# CONN.net
KiCad netlist of a schematic drawn in Altium Designer
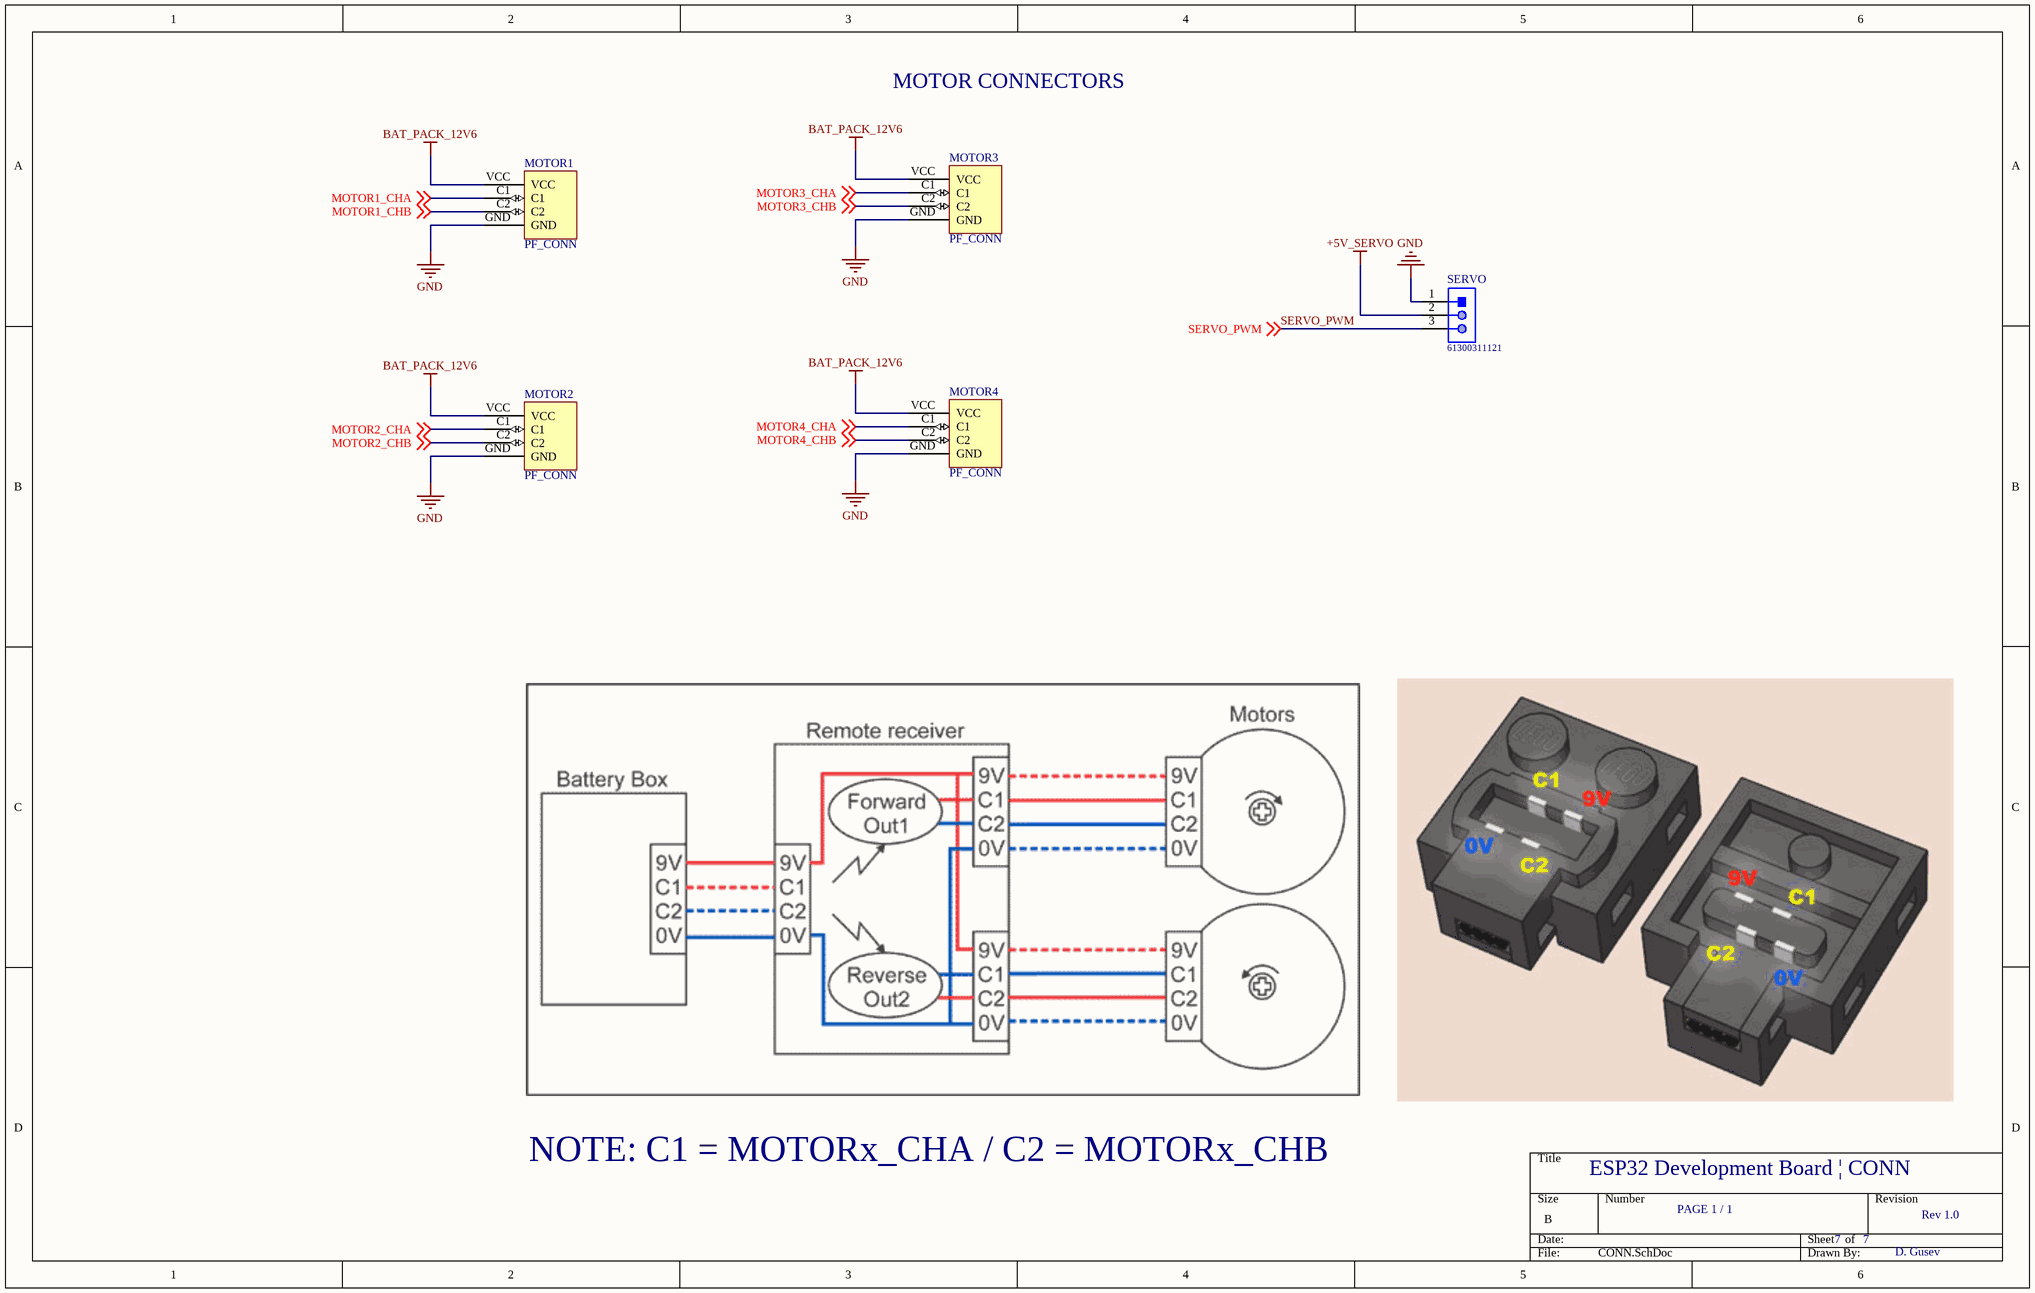
[diagram p0: CONN.SchDoc]

(export (version "E")
  (design (tool "Eeschema 10.0.6"))
  (components
    (comp (ref "MOTOR1")
      (value "PF_CONN")
      (footprint "PF_CONN")
      (libsource (lib "ddrlegobrick") (part "PF_CONN"))
    )
    (comp (ref "MOTOR2")
      (value "PF_CONN")
      (footprint "PF_CONN")
      (libsource (lib "ddrlegobrick") (part "PF_CONN"))
    )
    (comp (ref "MOTOR3")
      (value "PF_CONN")
      (footprint "PF_CONN")
      (libsource (lib "ddrlegobrick") (part "PF_CONN"))
    )
    (comp (ref "MOTOR4")
      (value "PF_CONN")
      (footprint "PF_CONN")
      (libsource (lib "ddrlegobrick") (part "PF_CONN"))
    )
    (comp (ref "SERVO")
      (value "61300311121")
      (footprint "61300311121")
      (description "THT Vertical Pin Header WR-PHD, Pitch 2.54 mm, Single Row, 3 pins")
      (fields (field (name "MANUFACTURER") "Wurth Elektronik") (field (name "PUBLISHER") "WurthElektronik"))
      (libsource (lib "Altium Content Vault") (part "WE-CN-1P-M-R3"))
    )
  )
  (nets
    (net (code "1") (name "+5V_SERVO") (class "Default")
      (node (ref "SERVO") (pin "2") (pinfunction "2_2") (pintype "passive"))
    )
    (net (code "2") (name "BAT_PACK_12V6") (class "Default")
      (node (ref "MOTOR1") (pin "VCC") (pinfunction "VCC_VCC") (pintype "power_in"))
      (node (ref "MOTOR2") (pin "VCC") (pinfunction "VCC_VCC") (pintype "power_in"))
      (node (ref "MOTOR3") (pin "VCC") (pinfunction "VCC_VCC") (pintype "power_in"))
      (node (ref "MOTOR4") (pin "VCC") (pinfunction "VCC_VCC") (pintype "power_in"))
    )
    (net (code "3") (name "GND") (class "Default")
      (node (ref "MOTOR1") (pin "GND") (pinfunction "GND_GND") (pintype "power_in"))
      (node (ref "MOTOR2") (pin "GND") (pinfunction "GND_GND") (pintype "power_in"))
      (node (ref "MOTOR3") (pin "GND") (pinfunction "GND_GND") (pintype "power_in"))
      (node (ref "MOTOR4") (pin "GND") (pinfunction "GND_GND") (pintype "power_in"))
      (node (ref "SERVO") (pin "1") (pinfunction "1_1") (pintype "passive"))
    )
    (net (code "4") (name "MOTOR1_CHA") (class "Default")
      (node (ref "MOTOR1") (pin "C1") (pinfunction "C1_C1") (pintype "bidirectional"))
    )
    (net (code "5") (name "MOTOR1_CHB") (class "Default")
      (node (ref "MOTOR1") (pin "C2") (pinfunction "C2_C2") (pintype "bidirectional"))
    )
    (net (code "6") (name "MOTOR2_CHA") (class "Default")
      (node (ref "MOTOR2") (pin "C1") (pinfunction "C1_C1") (pintype "bidirectional"))
    )
    (net (code "7") (name "MOTOR2_CHB") (class "Default")
      (node (ref "MOTOR2") (pin "C2") (pinfunction "C2_C2") (pintype "bidirectional"))
    )
    (net (code "8") (name "MOTOR3_CHA") (class "Default")
      (node (ref "MOTOR3") (pin "C1") (pinfunction "C1_C1") (pintype "bidirectional"))
    )
    (net (code "9") (name "MOTOR3_CHB") (class "Default")
      (node (ref "MOTOR3") (pin "C2") (pinfunction "C2_C2") (pintype "bidirectional"))
    )
    (net (code "10") (name "MOTOR4_CHA") (class "Default")
      (node (ref "MOTOR4") (pin "C1") (pinfunction "C1_C1") (pintype "bidirectional"))
    )
    (net (code "11") (name "MOTOR4_CHB") (class "Default")
      (node (ref "MOTOR4") (pin "C2") (pinfunction "C2_C2") (pintype "bidirectional"))
    )
    (net (code "12") (name "SERVO_PWM") (class "Default")
      (node (ref "SERVO") (pin "3") (pinfunction "3_3") (pintype "passive"))
    )
  )
)
